# STM32.net
KiCad netlist of a schematic drawn in Altium Designer
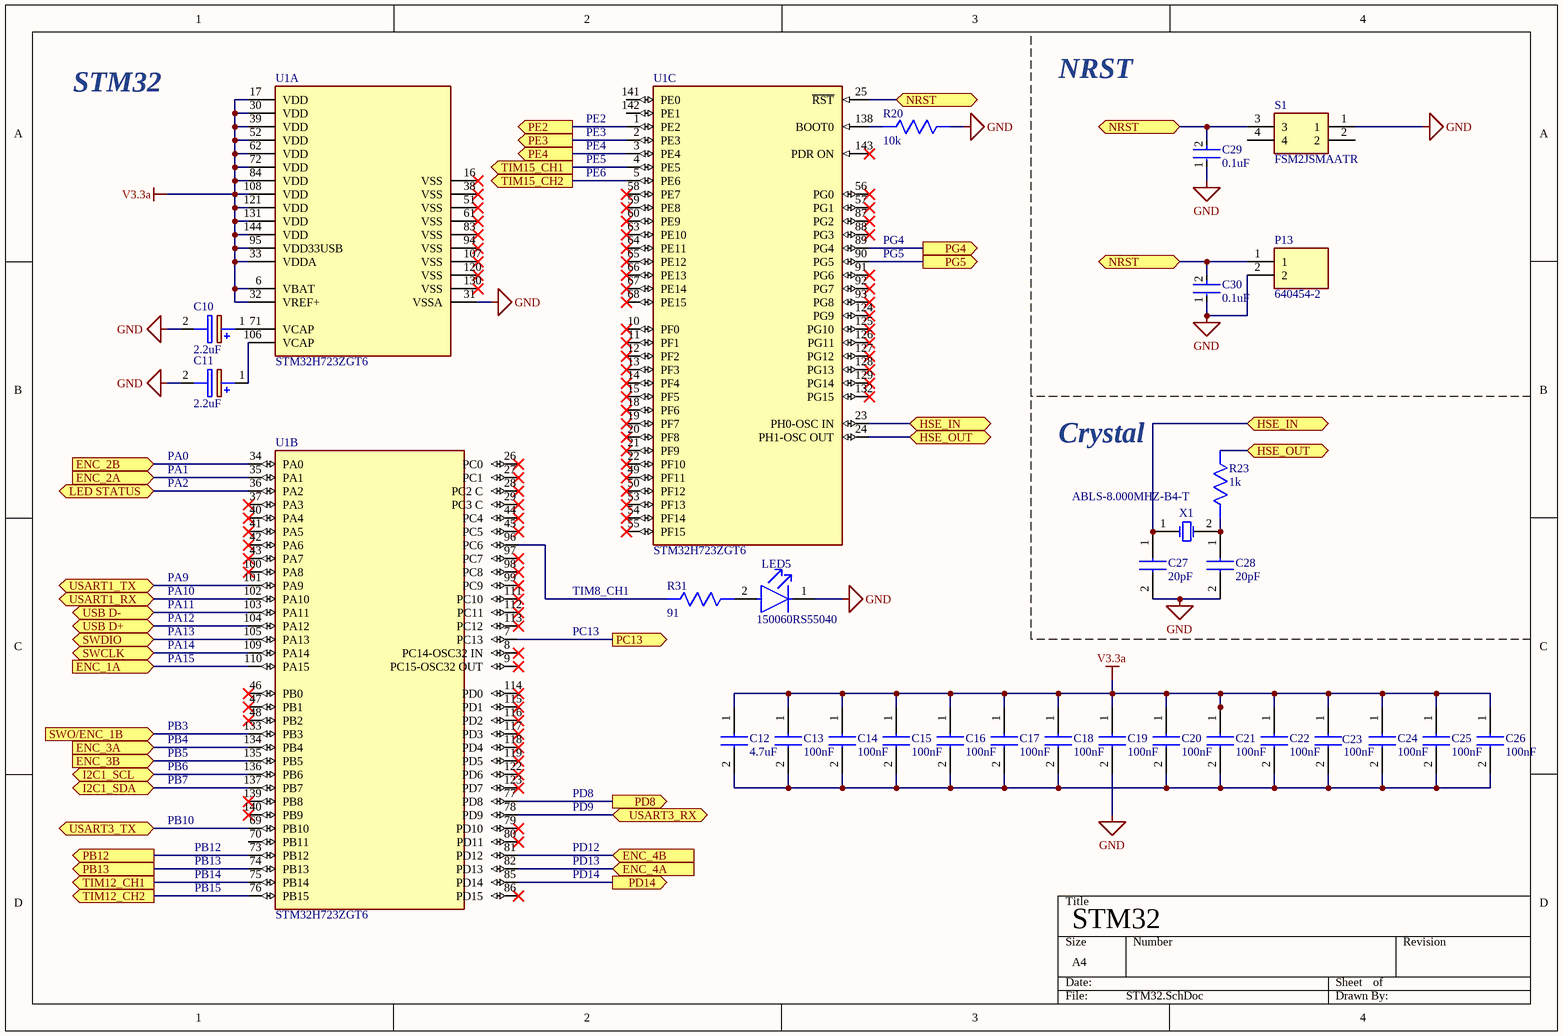
[diagram p0: STM32.SchDoc]

(export (version "E")
  (design (tool "Eeschema 10.0.6"))
  (components
    (comp (ref "C10")
      (value "2.2uF")
      (footprint "SamacSys:T491D")
      (description "Capacitor Polarised")
      (fields (field (name "MANUFACTURER_PART_NUMBER") "T491D225K050AH"))
      (libsource (lib "SamacSys") (part "T491D225K050AH"))
    )
    (comp (ref "C11")
      (value "2.2uF")
      (footprint "SamacSys:T491D")
      (description "Capacitor Polarised")
      (fields (field (name "MANUFACTURER_PART_NUMBER") "T491D225K050AH"))
      (libsource (lib "SamacSys") (part "T491D225K050AH"))
    )
    (comp (ref "C12")
      (value "4.7uF")
      (footprint "SamacSys:C1608_Commercial")
      (description "Capacitor")
      (fields (field (name "MANUFACTURER_PART_NUMBER") "C1608X5R1H104M080AA"))
      (libsource (lib "*") (part "C1608X5R1H104M080AA"))
    )
    (comp (ref "C13")
      (value "100nF")
      (footprint "SamacSys:C1608_Commercial")
      (description "Capacitor")
      (fields (field (name "MANUFACTURER_PART_NUMBER") "C1608X5R1H104M080AA"))
      (libsource (lib "*") (part "C1608X5R1H104M080AA"))
    )
    (comp (ref "C14")
      (value "100nF")
      (footprint "SamacSys:C1608_Commercial")
      (description "Capacitor")
      (fields (field (name "MANUFACTURER_PART_NUMBER") "C1608X5R1H104M080AA"))
      (libsource (lib "*") (part "C1608X5R1H104M080AA"))
    )
    (comp (ref "C15")
      (value "100nF")
      (footprint "SamacSys:C1608_Commercial")
      (description "Capacitor")
      (fields (field (name "MANUFACTURER_PART_NUMBER") "C1608X5R1H104M080AA"))
      (libsource (lib "*") (part "C1608X5R1H104M080AA"))
    )
    (comp (ref "C16")
      (value "100nF")
      (footprint "SamacSys:C1608_Commercial")
      (description "Capacitor")
      (fields (field (name "MANUFACTURER_PART_NUMBER") "C1608X5R1H104M080AA"))
      (libsource (lib "*") (part "C1608X5R1H104M080AA"))
    )
    (comp (ref "C17")
      (value "100nF")
      (footprint "SamacSys:C1608_Commercial")
      (description "Capacitor")
      (fields (field (name "MANUFACTURER_PART_NUMBER") "C1608X5R1H104M080AA"))
      (libsource (lib "*") (part "C1608X5R1H104M080AA"))
    )
    (comp (ref "C18")
      (value "100nF")
      (footprint "SamacSys:C1608_Commercial")
      (description "Capacitor")
      (fields (field (name "MANUFACTURER_PART_NUMBER") "C1608X5R1H104M080AA"))
      (libsource (lib "*") (part "C1608X5R1H104M080AA"))
    )
    (comp (ref "C19")
      (value "100nF")
      (footprint "SamacSys:C1608_Commercial")
      (description "Capacitor")
      (fields (field (name "MANUFACTURER_PART_NUMBER") "C1608X5R1H104M080AA"))
      (libsource (lib "*") (part "C1608X5R1H104M080AA"))
    )
    (comp (ref "C20")
      (value "100nF")
      (footprint "SamacSys:C1608_Commercial")
      (description "Capacitor")
      (fields (field (name "MANUFACTURER_PART_NUMBER") "C1608X5R1H104M080AA"))
      (libsource (lib "*") (part "C1608X5R1H104M080AA"))
    )
    (comp (ref "C21")
      (value "100nF")
      (footprint "SamacSys:C1608_Commercial")
      (description "Capacitor")
      (fields (field (name "MANUFACTURER_PART_NUMBER") "C1608X5R1H104M080AA"))
      (libsource (lib "*") (part "C1608X5R1H104M080AA"))
    )
    (comp (ref "C22")
      (value "100nF")
      (footprint "SamacSys:C1608_Commercial")
      (description "Capacitor")
      (fields (field (name "MANUFACTURER_PART_NUMBER") "C1608X5R1H104M080AA"))
      (libsource (lib "*") (part "C1608X5R1H104M080AA"))
    )
    (comp (ref "C23")
      (value "100nF")
      (footprint "SamacSys:C1608_Commercial")
      (description "Capacitor")
      (fields (field (name "MANUFACTURER_PART_NUMBER") "C1608X5R1H104M080AA"))
      (libsource (lib "*") (part "C1608X5R1H104M080AA"))
    )
    (comp (ref "C24")
      (value "100nF")
      (footprint "SamacSys:C1608_Commercial")
      (description "Capacitor")
      (fields (field (name "MANUFACTURER_PART_NUMBER") "C1608X5R1H104M080AA"))
      (libsource (lib "*") (part "C1608X5R1H104M080AA"))
    )
    (comp (ref "C25")
      (value "100nF")
      (footprint "SamacSys:C1608_Commercial")
      (description "Capacitor")
      (fields (field (name "MANUFACTURER_PART_NUMBER") "C1608X5R1H104M080AA"))
      (libsource (lib "*") (part "C1608X5R1H104M080AA"))
    )
    (comp (ref "C26")
      (value "100nF")
      (footprint "SamacSys:C1608_Commercial")
      (description "Capacitor")
      (fields (field (name "MANUFACTURER_PART_NUMBER") "C1608X5R1H104M080AA"))
      (libsource (lib "*") (part "C1608X5R1H104M080AA"))
    )
    (comp (ref "C27")
      (value "20pF")
      (footprint "SamacSys:CAPC1608X90N")
      (description "Capacitor")
      (fields
        (field (name "MANUFACTURER_PART_NUMBER") "06035A200FAT2A")
        (field (name "MOUSER PART NUMBER") "581-06035A200FAT2A")
      )
      (libsource (lib "*") (part "06035A200FAT2A"))
    )
    (comp (ref "C28")
      (value "20pF")
      (footprint "SamacSys:CAPC1608X90N")
      (description "Capacitor")
      (fields
        (field (name "MANUFACTURER_PART_NUMBER") "06035A200FAT2A")
        (field (name "MOUSER PART NUMBER") "581-06035A200FAT2A")
      )
      (libsource (lib "*") (part "06035A200FAT2A"))
    )
    (comp (ref "C29")
      (value "0.1uF")
      (footprint "FP-C1608-080-0_1-IPC_A")
      (description "Multilayer Ceramic Capacitors 100nF ±10% 50V X5R SMD 0603")
      (fields (field (name "TOLERANCE") "10%"))
      (libsource (lib "Altium Content Vault") (part "236180d848d6139a670b325ea6854c9"))
    )
    (comp (ref "C30")
      (value "0.1uF")
      (footprint "FP-C1608-080-0_1-IPC_A")
      (description "Multilayer Ceramic Capacitors 100nF ±10% 50V X5R SMD 0603")
      (fields (field (name "TOLERANCE") "10%"))
      (libsource (lib "Altium Content Vault") (part "236180d848d6139a670b325ea6854c9"))
    )
    (comp (ref "LED5")
      (value "150060RS55040")
      (footprint "FP-150060RS55040-MFG")
      (description "LED RED DIFFUSED 0603 SMD")
      (libsource (lib "Altium Content Vault") (part "8706943c75ba83719d021d2fdc84c58"))
    )
    (comp (ref "P13")
      (value "640454-2")
      (footprint "SamacSys:HDRV2W66P0X254_1X2_762X572X1003P")
      (description "Connector")
      (libsource (lib "*") (part "640454-2"))
    )
    (comp (ref "R20")
      (value "10k")
      (footprint "SamacSys:RESC1608X55N")
      (description "Resistor")
      (fields (field (name "MANUFACTURER_PART_NUMBER") "CMP0603-FX-1003ELF"))
      (libsource (lib "SamacSys") (part "CMP0603-FX-1003ELF"))
    )
    (comp (ref "R23")
      (value "1k")
      (footprint "SamacSys:RESC1608X55N")
      (description "Resistor")
      (fields (field (name "MANUFACTURER_PART_NUMBER") "CMP0603-FX-1003ELF"))
      (libsource (lib "SamacSys") (part "CMP0603-FX-1003ELF"))
    )
    (comp (ref "R31")
      (value "91")
      (footprint "SamacSys:RESC1608X55N")
      (description "Resistor")
      (fields (field (name "MANUFACTURER_PART_NUMBER") "CMP0603-FX-1003ELF"))
      (libsource (lib "SamacSys") (part "CMP0603-FX-1003ELF"))
    )
    (comp (ref "S1")
      (value "FSM2JSMAATR")
      (footprint "SamacSys:FSM2J_1")
      (description "Switch")
      (libsource (lib "SamacSys") (part "FSM2JSMAATR"))
    )
    (comp (ref "U1")
      (value "STM32H723ZGT6")
      (footprint "FP-LQFP144-1A-IPC_C")
      (description "IC MCU 32BIT 1MB FLASH 144LQFP")
      (libsource (lib "Altium Content Vault") (part "099c9e622ff36f7eb897f9cba6d1f51"))
    )
    (comp (ref "X1")
      (value "ABLS-8.000MHZ-B4-T")
      (footprint "ABRA-ABLS-14.7456MHZ-B2-T_V")
      (description "Low Profile Crystal, 8.0 MHz, +/- 30 ppm, -20 to 70 degC, 2-Pin SMD, RoHS, Tape and Reel")
      (fields (field (name "MANUFACTURER") "ABRACON") (field (name "TOLERANCE") "30PPM"))
      (libsource (lib "Altium Content Vault") (part "XTAL_1-2-2"))
    )
  )
  (nets
    (net (code "1") (name "/ENC_1A") (class "Default")
      (node (ref "U1") (pin "110") (pinfunction "PA15_110") (pintype "bidirectional"))
    )
    (net (code "2") (name "/ENC_2A") (class "Default")
      (node (ref "U1") (pin "35") (pinfunction "PA1_35") (pintype "bidirectional"))
    )
    (net (code "3") (name "/ENC_2B") (class "Default")
      (node (ref "U1") (pin "34") (pinfunction "PA0_34") (pintype "bidirectional"))
    )
    (net (code "4") (name "/ENC_3A") (class "Default")
      (node (ref "U1") (pin "134") (pinfunction "PB4_134") (pintype "bidirectional"))
    )
    (net (code "5") (name "/ENC_3B") (class "Default")
      (node (ref "U1") (pin "135") (pinfunction "PB5_135") (pintype "bidirectional"))
    )
    (net (code "6") (name "/ENC_4A") (class "Default")
      (node (ref "U1") (pin "82") (pinfunction "PD13_82") (pintype "bidirectional"))
    )
    (net (code "7") (name "/ENC_4B") (class "Default")
      (node (ref "U1") (pin "81") (pinfunction "PD12_81") (pintype "bidirectional"))
    )
    (net (code "8") (name "/HSE_IN") (class "Default")
      (node (ref "C27") (pin "1") (pinfunction "1_1") (pintype "passive"))
      (node (ref "U1") (pin "23") (pinfunction "PH0-OSC_IN_23") (pintype "bidirectional"))
      (node (ref "X1") (pin "1") (pinfunction "X1_1") (pintype "passive"))
    )
    (net (code "9") (name "/HSE_OUT") (class "Default")
      (node (ref "R23") (pin "2") (pinfunction "2_2") (pintype "passive"))
      (node (ref "U1") (pin "24") (pinfunction "PH1-OSC_OUT_24") (pintype "bidirectional"))
    )
    (net (code "10") (name "/I2C1_SCL") (class "Default")
      (node (ref "U1") (pin "136") (pinfunction "PB6_136") (pintype "bidirectional"))
    )
    (net (code "11") (name "/I2C1_SDA") (class "Default")
      (node (ref "U1") (pin "137") (pinfunction "PB7_137") (pintype "bidirectional"))
    )
    (net (code "12") (name "/LED STATUS") (class "Default")
      (node (ref "U1") (pin "36") (pinfunction "PA2_36") (pintype "bidirectional"))
    )
    (net (code "13") (name "/NRST") (class "Default")
      (node (ref "C29") (pin "2") (pinfunction "2_2") (pintype "passive"))
      (node (ref "C30") (pin "2") (pinfunction "2_2") (pintype "passive"))
      (node (ref "P13") (pin "1") (pinfunction "1_1") (pintype "passive"))
      (node (ref "S1") (pin "3") (pinfunction "3_3") (pintype "passive"))
      (node (ref "U1") (pin "25") (pinfunction "~{RST}_25") (pintype "input"))
    )
    (net (code "14") (name "/PB12") (class "Default")
      (node (ref "U1") (pin "73") (pinfunction "PB12_73") (pintype "bidirectional"))
    )
    (net (code "15") (name "/PB13") (class "Default")
      (node (ref "U1") (pin "74") (pinfunction "PB13_74") (pintype "bidirectional"))
    )
    (net (code "16") (name "/PC13") (class "Default")
      (node (ref "U1") (pin "7") (pinfunction "PC13_7") (pintype "bidirectional"))
    )
    (net (code "17") (name "/PD8") (class "Default")
      (node (ref "U1") (pin "77") (pinfunction "PD8_77") (pintype "bidirectional"))
    )
    (net (code "18") (name "/PD14") (class "Default")
      (node (ref "U1") (pin "85") (pinfunction "PD14_85") (pintype "bidirectional"))
    )
    (net (code "19") (name "/PE2") (class "Default")
      (node (ref "U1") (pin "1") (pinfunction "PE2_1") (pintype "bidirectional"))
    )
    (net (code "20") (name "/PE3") (class "Default")
      (node (ref "U1") (pin "2") (pinfunction "PE3_2") (pintype "bidirectional"))
    )
    (net (code "21") (name "/PE4") (class "Default")
      (node (ref "U1") (pin "3") (pinfunction "PE4_3") (pintype "bidirectional"))
    )
    (net (code "22") (name "/PG4") (class "Default")
      (node (ref "U1") (pin "89") (pinfunction "PG4_89") (pintype "bidirectional"))
    )
    (net (code "23") (name "/PG5") (class "Default")
      (node (ref "U1") (pin "90") (pinfunction "PG5_90") (pintype "bidirectional"))
    )
    (net (code "24") (name "/SWCLK") (class "Default")
      (node (ref "U1") (pin "109") (pinfunction "PA14_109") (pintype "bidirectional"))
    )
    (net (code "25") (name "/SWDIO") (class "Default")
      (node (ref "U1") (pin "105") (pinfunction "PA13_105") (pintype "bidirectional"))
    )
    (net (code "26") (name "/SWO{slash}ENC_1B") (class "Default")
      (node (ref "U1") (pin "133") (pinfunction "PB3_133") (pintype "bidirectional"))
    )
    (net (code "27") (name "/TIM12_CH1") (class "Default")
      (node (ref "U1") (pin "75") (pinfunction "PB14_75") (pintype "bidirectional"))
    )
    (net (code "28") (name "/TIM12_CH2") (class "Default")
      (node (ref "U1") (pin "76") (pinfunction "PB15_76") (pintype "bidirectional"))
    )
    (net (code "29") (name "/TIM15_CH1") (class "Default")
      (node (ref "U1") (pin "4") (pinfunction "PE5_4") (pintype "bidirectional"))
    )
    (net (code "30") (name "/TIM15_CH2") (class "Default")
      (node (ref "U1") (pin "5") (pinfunction "PE6_5") (pintype "bidirectional"))
    )
    (net (code "31") (name "/USART1_RX") (class "Default")
      (node (ref "U1") (pin "102") (pinfunction "PA10_102") (pintype "bidirectional"))
    )
    (net (code "32") (name "/USART1_TX") (class "Default")
      (node (ref "U1") (pin "101") (pinfunction "PA9_101") (pintype "bidirectional"))
    )
    (net (code "33") (name "/USART3_RX") (class "Default")
      (node (ref "U1") (pin "78") (pinfunction "PD9_78") (pintype "bidirectional"))
    )
    (net (code "34") (name "/USART3_TX") (class "Default")
      (node (ref "U1") (pin "69") (pinfunction "PB10_69") (pintype "bidirectional"))
    )
    (net (code "35") (name "/USB D+") (class "Default")
      (node (ref "U1") (pin "104") (pinfunction "PA12_104") (pintype "bidirectional"))
    )
    (net (code "36") (name "/USB D-") (class "Default")
      (node (ref "U1") (pin "103") (pinfunction "PA11_103") (pintype "bidirectional"))
    )
    (net (code "37") (name "GND") (class "Default")
      (node (ref "C10") (pin "2") (pinfunction "-_2") (pintype "passive"))
      (node (ref "C11") (pin "2") (pinfunction "-_2") (pintype "passive"))
      (node (ref "C19") (pin "2") (pinfunction "2_2") (pintype "passive"))
      (node (ref "C27") (pin "2") (pinfunction "2_2") (pintype "passive"))
      (node (ref "C28") (pin "2") (pinfunction "2_2") (pintype "passive"))
      (node (ref "C29") (pin "1") (pinfunction "1_1") (pintype "passive"))
      (node (ref "C30") (pin "1") (pinfunction "1_1") (pintype "passive"))
      (node (ref "LED5") (pin "1") (pinfunction "C_1") (pintype "passive"))
      (node (ref "P13") (pin "2") (pinfunction "2_2") (pintype "passive"))
      (node (ref "R20") (pin "2") (pinfunction "2_2") (pintype "passive"))
      (node (ref "S1") (pin "1") (pinfunction "1_1") (pintype "passive"))
      (node (ref "U1") (pin "31") (pinfunction "VSSA_31") (pintype "power_in"))
    )
    (net (code "38") (name "Net-(C10-+)") (class "Default")
      (node (ref "C10") (pin "1") (pinfunction "+_1") (pintype "passive"))
      (node (ref "U1") (pin "71") (pinfunction "VCAP_71") (pintype "power_in"))
    )
    (net (code "39") (name "Net-(C11-+)") (class "Default")
      (node (ref "C11") (pin "1") (pinfunction "+_1") (pintype "passive"))
      (node (ref "U1") (pin "106") (pinfunction "VCAP_106") (pintype "power_in"))
    )
    (net (code "40") (name "Net-(C12-Pad2)") (class "Default")
      (node (ref "C12") (pin "2") (pinfunction "2_2") (pintype "passive"))
      (node (ref "C13") (pin "2") (pinfunction "2_2") (pintype "passive"))
      (node (ref "C14") (pin "2") (pinfunction "2_2") (pintype "passive"))
      (node (ref "C15") (pin "2") (pinfunction "2_2") (pintype "passive"))
      (node (ref "C16") (pin "2") (pinfunction "2_2") (pintype "passive"))
      (node (ref "C17") (pin "2") (pinfunction "2_2") (pintype "passive"))
      (node (ref "C18") (pin "2") (pinfunction "2_2") (pintype "passive"))
      (node (ref "C20") (pin "2") (pinfunction "2_2") (pintype "passive"))
      (node (ref "C21") (pin "2") (pinfunction "2_2") (pintype "passive"))
      (node (ref "C22") (pin "2") (pinfunction "2_2") (pintype "passive"))
      (node (ref "C23") (pin "2") (pinfunction "2_2") (pintype "passive"))
      (node (ref "C24") (pin "2") (pinfunction "2_2") (pintype "passive"))
      (node (ref "C25") (pin "2") (pinfunction "2_2") (pintype "passive"))
      (node (ref "C26") (pin "2") (pinfunction "2_2") (pintype "passive"))
    )
    (net (code "41") (name "Net-(LED5-A)") (class "Default")
      (node (ref "LED5") (pin "2") (pinfunction "A_2") (pintype "passive"))
      (node (ref "R31") (pin "2") (pinfunction "2_2") (pintype "passive"))
    )
    (net (code "42") (name "Net-(U1B-PC6)") (class "Default")
      (node (ref "R31") (pin "1") (pinfunction "1_1") (pintype "passive"))
      (node (ref "U1") (pin "96") (pinfunction "PC6_96") (pintype "bidirectional"))
    )
    (net (code "43") (name "Net-(U1C-BOOT0)") (class "Default")
      (node (ref "R20") (pin "1") (pinfunction "1_1") (pintype "passive"))
      (node (ref "U1") (pin "138") (pinfunction "BOOT0_138") (pintype "input"))
    )
    (net (code "44") (name "Net-(X1-X2)") (class "Default")
      (node (ref "C28") (pin "1") (pinfunction "1_1") (pintype "passive"))
      (node (ref "R23") (pin "1") (pinfunction "1_1") (pintype "passive"))
      (node (ref "X1") (pin "2") (pinfunction "X2_2") (pintype "passive"))
    )
    (net (code "45") (name "V3.3a") (class "Default")
      (node (ref "C12") (pin "1") (pinfunction "1_1") (pintype "passive"))
      (node (ref "C13") (pin "1") (pinfunction "1_1") (pintype "passive"))
      (node (ref "C14") (pin "1") (pinfunction "1_1") (pintype "passive"))
      (node (ref "C15") (pin "1") (pinfunction "1_1") (pintype "passive"))
      (node (ref "C16") (pin "1") (pinfunction "1_1") (pintype "passive"))
      (node (ref "C17") (pin "1") (pinfunction "1_1") (pintype "passive"))
      (node (ref "C18") (pin "1") (pinfunction "1_1") (pintype "passive"))
      (node (ref "C19") (pin "1") (pinfunction "1_1") (pintype "passive"))
      (node (ref "C20") (pin "1") (pinfunction "1_1") (pintype "passive"))
      (node (ref "C21") (pin "1") (pinfunction "1_1") (pintype "passive"))
      (node (ref "C22") (pin "1") (pinfunction "1_1") (pintype "passive"))
      (node (ref "C23") (pin "1") (pinfunction "1_1") (pintype "passive"))
      (node (ref "C24") (pin "1") (pinfunction "1_1") (pintype "passive"))
      (node (ref "C25") (pin "1") (pinfunction "1_1") (pintype "passive"))
      (node (ref "C26") (pin "1") (pinfunction "1_1") (pintype "passive"))
      (node (ref "U1") (pin "108") (pinfunction "VDD_108") (pintype "power_in"))
      (node (ref "U1") (pin "121") (pinfunction "VDD_121") (pintype "power_in"))
      (node (ref "U1") (pin "131") (pinfunction "VDD_131") (pintype "power_in"))
      (node (ref "U1") (pin "144") (pinfunction "VDD_144") (pintype "power_in"))
      (node (ref "U1") (pin "17") (pinfunction "VDD_17") (pintype "power_in"))
      (node (ref "U1") (pin "30") (pinfunction "VDD_30") (pintype "power_in"))
      (node (ref "U1") (pin "32") (pinfunction "VREF+_32") (pintype "power_in"))
      (node (ref "U1") (pin "33") (pinfunction "VDDA_33") (pintype "power_in"))
      (node (ref "U1") (pin "39") (pinfunction "VDD_39") (pintype "power_in"))
      (node (ref "U1") (pin "52") (pinfunction "VDD_52") (pintype "power_in"))
      (node (ref "U1") (pin "6") (pinfunction "VBAT_6") (pintype "power_in"))
      (node (ref "U1") (pin "62") (pinfunction "VDD_62") (pintype "power_in"))
      (node (ref "U1") (pin "72") (pinfunction "VDD_72") (pintype "power_in"))
      (node (ref "U1") (pin "84") (pinfunction "VDD_84") (pintype "power_in"))
      (node (ref "U1") (pin "95") (pinfunction "VDD33USB_95") (pintype "power_in"))
    )
    (net (code "46") (name "unconnected-(S1-Pad2)") (class "Default")
      (node (ref "S1") (pin "2") (pinfunction "2_2") (pintype "passive"))
    )
    (net (code "47") (name "unconnected-(S1-Pad4)") (class "Default")
      (node (ref "S1") (pin "4") (pinfunction "4_4") (pintype "passive"))
    )
    (net (code "48") (name "unconnected-(U1A-VSS-Pad16)") (class "Default")
      (node (ref "U1") (pin "16") (pinfunction "VSS_16") (pintype "power_in+no_connect"))
    )
    (net (code "49") (name "unconnected-(U1A-VSS-Pad38)") (class "Default")
      (node (ref "U1") (pin "38") (pinfunction "VSS_38") (pintype "power_in+no_connect"))
    )
    (net (code "50") (name "unconnected-(U1A-VSS-Pad51)") (class "Default")
      (node (ref "U1") (pin "51") (pinfunction "VSS_51") (pintype "power_in+no_connect"))
    )
    (net (code "51") (name "unconnected-(U1A-VSS-Pad61)") (class "Default")
      (node (ref "U1") (pin "61") (pinfunction "VSS_61") (pintype "power_in+no_connect"))
    )
    (net (code "52") (name "unconnected-(U1A-VSS-Pad83)") (class "Default")
      (node (ref "U1") (pin "83") (pinfunction "VSS_83") (pintype "power_in+no_connect"))
    )
    (net (code "53") (name "unconnected-(U1A-VSS-Pad94)") (class "Default")
      (node (ref "U1") (pin "94") (pinfunction "VSS_94") (pintype "power_in+no_connect"))
    )
    (net (code "54") (name "unconnected-(U1A-VSS-Pad107)") (class "Default")
      (node (ref "U1") (pin "107") (pinfunction "VSS_107") (pintype "power_in+no_connect"))
    )
    (net (code "55") (name "unconnected-(U1A-VSS-Pad120)") (class "Default")
      (node (ref "U1") (pin "120") (pinfunction "VSS_120") (pintype "power_in+no_connect"))
    )
    (net (code "56") (name "unconnected-(U1A-VSS-Pad130)") (class "Default")
      (node (ref "U1") (pin "130") (pinfunction "VSS_130") (pintype "power_in+no_connect"))
    )
    (net (code "57") (name "unconnected-(U1B-PA3-Pad37)") (class "Default")
      (node (ref "U1") (pin "37") (pinfunction "PA3_37") (pintype "bidirectional+no_connect"))
    )
    (net (code "58") (name "unconnected-(U1B-PA4-Pad40)") (class "Default")
      (node (ref "U1") (pin "40") (pinfunction "PA4_40") (pintype "bidirectional+no_connect"))
    )
    (net (code "59") (name "unconnected-(U1B-PA5-Pad41)") (class "Default")
      (node (ref "U1") (pin "41") (pinfunction "PA5_41") (pintype "bidirectional+no_connect"))
    )
    (net (code "60") (name "unconnected-(U1B-PA6-Pad42)") (class "Default")
      (node (ref "U1") (pin "42") (pinfunction "PA6_42") (pintype "bidirectional+no_connect"))
    )
    (net (code "61") (name "unconnected-(U1B-PA7-Pad43)") (class "Default")
      (node (ref "U1") (pin "43") (pinfunction "PA7_43") (pintype "bidirectional+no_connect"))
    )
    (net (code "62") (name "unconnected-(U1B-PA8-Pad100)") (class "Default")
      (node (ref "U1") (pin "100") (pinfunction "PA8_100") (pintype "bidirectional+no_connect"))
    )
    (net (code "63") (name "unconnected-(U1B-PB0-Pad46)") (class "Default")
      (node (ref "U1") (pin "46") (pinfunction "PB0_46") (pintype "bidirectional+no_connect"))
    )
    (net (code "64") (name "unconnected-(U1B-PB1-Pad47)") (class "Default")
      (node (ref "U1") (pin "47") (pinfunction "PB1_47") (pintype "bidirectional+no_connect"))
    )
    (net (code "65") (name "unconnected-(U1B-PB2-Pad48)") (class "Default")
      (node (ref "U1") (pin "48") (pinfunction "PB2_48") (pintype "bidirectional+no_connect"))
    )
    (net (code "66") (name "unconnected-(U1B-PB8-Pad139)") (class "Default")
      (node (ref "U1") (pin "139") (pinfunction "PB8_139") (pintype "bidirectional+no_connect"))
    )
    (net (code "67") (name "unconnected-(U1B-PB9-Pad140)") (class "Default")
      (node (ref "U1") (pin "140") (pinfunction "PB9_140") (pintype "bidirectional+no_connect"))
    )
    (net (code "68") (name "unconnected-(U1B-PB11-Pad70)") (class "Default")
      (node (ref "U1") (pin "70") (pinfunction "PB11_70") (pintype "bidirectional"))
    )
    (net (code "69") (name "unconnected-(U1B-PC0-Pad26)") (class "Default")
      (node (ref "U1") (pin "26") (pinfunction "PC0_26") (pintype "bidirectional+no_connect"))
    )
    (net (code "70") (name "unconnected-(U1B-PC1-Pad27)") (class "Default")
      (node (ref "U1") (pin "27") (pinfunction "PC1_27") (pintype "bidirectional+no_connect"))
    )
    (net (code "71") (name "unconnected-(U1B-PC2_C-Pad28)") (class "Default")
      (node (ref "U1") (pin "28") (pinfunction "PC2_C_28") (pintype "bidirectional+no_connect"))
    )
    (net (code "72") (name "unconnected-(U1B-PC3_C-Pad29)") (class "Default")
      (node (ref "U1") (pin "29") (pinfunction "PC3_C_29") (pintype "bidirectional+no_connect"))
    )
    (net (code "73") (name "unconnected-(U1B-PC4-Pad44)") (class "Default")
      (node (ref "U1") (pin "44") (pinfunction "PC4_44") (pintype "bidirectional+no_connect"))
    )
    (net (code "74") (name "unconnected-(U1B-PC5-Pad45)") (class "Default")
      (node (ref "U1") (pin "45") (pinfunction "PC5_45") (pintype "bidirectional+no_connect"))
    )
    (net (code "75") (name "unconnected-(U1B-PC7-Pad97)") (class "Default")
      (node (ref "U1") (pin "97") (pinfunction "PC7_97") (pintype "bidirectional+no_connect"))
    )
    (net (code "76") (name "unconnected-(U1B-PC8-Pad98)") (class "Default")
      (node (ref "U1") (pin "98") (pinfunction "PC8_98") (pintype "bidirectional+no_connect"))
    )
    (net (code "77") (name "unconnected-(U1B-PC9-Pad99)") (class "Default")
      (node (ref "U1") (pin "99") (pinfunction "PC9_99") (pintype "bidirectional+no_connect"))
    )
    (net (code "78") (name "unconnected-(U1B-PC10-Pad111)") (class "Default")
      (node (ref "U1") (pin "111") (pinfunction "PC10_111") (pintype "bidirectional+no_connect"))
    )
    (net (code "79") (name "unconnected-(U1B-PC11-Pad112)") (class "Default")
      (node (ref "U1") (pin "112") (pinfunction "PC11_112") (pintype "bidirectional+no_connect"))
    )
    (net (code "80") (name "unconnected-(U1B-PC12-Pad113)") (class "Default")
      (node (ref "U1") (pin "113") (pinfunction "PC12_113") (pintype "bidirectional+no_connect"))
    )
    (net (code "81") (name "unconnected-(U1B-PC14-OSC32_IN-Pad8)") (class "Default")
      (node (ref "U1") (pin "8") (pinfunction "PC14-OSC32_IN_8") (pintype "bidirectional+no_connect"))
    )
    (net (code "82") (name "unconnected-(U1B-PC15-OSC32_OUT-Pad9)") (class "Default")
      (node (ref "U1") (pin "9") (pinfunction "PC15-OSC32_OUT_9") (pintype "bidirectional+no_connect"))
    )
    (net (code "83") (name "unconnected-(U1B-PD0-Pad114)") (class "Default")
      (node (ref "U1") (pin "114") (pinfunction "PD0_114") (pintype "bidirectional+no_connect"))
    )
    (net (code "84") (name "unconnected-(U1B-PD1-Pad115)") (class "Default")
      (node (ref "U1") (pin "115") (pinfunction "PD1_115") (pintype "bidirectional+no_connect"))
    )
    (net (code "85") (name "unconnected-(U1B-PD2-Pad116)") (class "Default")
      (node (ref "U1") (pin "116") (pinfunction "PD2_116") (pintype "bidirectional+no_connect"))
    )
    (net (code "86") (name "unconnected-(U1B-PD3-Pad117)") (class "Default")
      (node (ref "U1") (pin "117") (pinfunction "PD3_117") (pintype "bidirectional+no_connect"))
    )
    (net (code "87") (name "unconnected-(U1B-PD4-Pad118)") (class "Default")
      (node (ref "U1") (pin "118") (pinfunction "PD4_118") (pintype "bidirectional+no_connect"))
    )
    (net (code "88") (name "unconnected-(U1B-PD5-Pad119)") (class "Default")
      (node (ref "U1") (pin "119") (pinfunction "PD5_119") (pintype "bidirectional+no_connect"))
    )
    (net (code "89") (name "unconnected-(U1B-PD6-Pad122)") (class "Default")
      (node (ref "U1") (pin "122") (pinfunction "PD6_122") (pintype "bidirectional+no_connect"))
    )
    (net (code "90") (name "unconnected-(U1B-PD7-Pad123)") (class "Default")
      (node (ref "U1") (pin "123") (pinfunction "PD7_123") (pintype "bidirectional+no_connect"))
    )
    (net (code "91") (name "unconnected-(U1B-PD10-Pad79)") (class "Default")
      (node (ref "U1") (pin "79") (pinfunction "PD10_79") (pintype "bidirectional+no_connect"))
    )
    (net (code "92") (name "unconnected-(U1B-PD11-Pad80)") (class "Default")
      (node (ref "U1") (pin "80") (pinfunction "PD11_80") (pintype "bidirectional+no_connect"))
    )
    (net (code "93") (name "unconnected-(U1B-PD15-Pad86)") (class "Default")
      (node (ref "U1") (pin "86") (pinfunction "PD15_86") (pintype "bidirectional+no_connect"))
    )
    (net (code "94") (name "unconnected-(U1C-PDR_ON-Pad143)") (class "Default")
      (node (ref "U1") (pin "143") (pinfunction "PDR_ON_143") (pintype "input+no_connect"))
    )
    (net (code "95") (name "unconnected-(U1C-PE0-Pad141)") (class "Default")
      (node (ref "U1") (pin "141") (pinfunction "PE0_141") (pintype "bidirectional"))
    )
    (net (code "96") (name "unconnected-(U1C-PE1-Pad142)") (class "Default")
      (node (ref "U1") (pin "142") (pinfunction "PE1_142") (pintype "bidirectional"))
    )
    (net (code "97") (name "unconnected-(U1C-PE7-Pad58)") (class "Default")
      (node (ref "U1") (pin "58") (pinfunction "PE7_58") (pintype "bidirectional+no_connect"))
    )
    (net (code "98") (name "unconnected-(U1C-PE8-Pad59)") (class "Default")
      (node (ref "U1") (pin "59") (pinfunction "PE8_59") (pintype "bidirectional+no_connect"))
    )
    (net (code "99") (name "unconnected-(U1C-PE9-Pad60)") (class "Default")
      (node (ref "U1") (pin "60") (pinfunction "PE9_60") (pintype "bidirectional+no_connect"))
    )
    (net (code "100") (name "unconnected-(U1C-PE10-Pad63)") (class "Default")
      (node (ref "U1") (pin "63") (pinfunction "PE10_63") (pintype "bidirectional+no_connect"))
    )
    (net (code "101") (name "unconnected-(U1C-PE11-Pad64)") (class "Default")
      (node (ref "U1") (pin "64") (pinfunction "PE11_64") (pintype "bidirectional+no_connect"))
    )
    (net (code "102") (name "unconnected-(U1C-PE12-Pad65)") (class "Default")
      (node (ref "U1") (pin "65") (pinfunction "PE12_65") (pintype "bidirectional+no_connect"))
    )
    (net (code "103") (name "unconnected-(U1C-PE13-Pad66)") (class "Default")
      (node (ref "U1") (pin "66") (pinfunction "PE13_66") (pintype "bidirectional+no_connect"))
    )
    (net (code "104") (name "unconnected-(U1C-PE14-Pad67)") (class "Default")
      (node (ref "U1") (pin "67") (pinfunction "PE14_67") (pintype "bidirectional+no_connect"))
    )
    (net (code "105") (name "unconnected-(U1C-PE15-Pad68)") (class "Default")
      (node (ref "U1") (pin "68") (pinfunction "PE15_68") (pintype "bidirectional+no_connect"))
    )
    (net (code "106") (name "unconnected-(U1C-PF0-Pad10)") (class "Default")
      (node (ref "U1") (pin "10") (pinfunction "PF0_10") (pintype "bidirectional+no_connect"))
    )
    (net (code "107") (name "unconnected-(U1C-PF1-Pad11)") (class "Default")
      (node (ref "U1") (pin "11") (pinfunction "PF1_11") (pintype "bidirectional+no_connect"))
    )
    (net (code "108") (name "unconnected-(U1C-PF2-Pad12)") (class "Default")
      (node (ref "U1") (pin "12") (pinfunction "PF2_12") (pintype "bidirectional+no_connect"))
    )
    (net (code "109") (name "unconnected-(U1C-PF3-Pad13)") (class "Default")
      (node (ref "U1") (pin "13") (pinfunction "PF3_13") (pintype "bidirectional+no_connect"))
    )
    (net (code "110") (name "unconnected-(U1C-PF4-Pad14)") (class "Default")
      (node (ref "U1") (pin "14") (pinfunction "PF4_14") (pintype "bidirectional+no_connect"))
    )
    (net (code "111") (name "unconnected-(U1C-PF5-Pad15)") (class "Default")
      (node (ref "U1") (pin "15") (pinfunction "PF5_15") (pintype "bidirectional+no_connect"))
    )
    (net (code "112") (name "unconnected-(U1C-PF6-Pad18)") (class "Default")
      (node (ref "U1") (pin "18") (pinfunction "PF6_18") (pintype "bidirectional+no_connect"))
    )
    (net (code "113") (name "unconnected-(U1C-PF7-Pad19)") (class "Default")
      (node (ref "U1") (pin "19") (pinfunction "PF7_19") (pintype "bidirectional+no_connect"))
    )
    (net (code "114") (name "unconnected-(U1C-PF8-Pad20)") (class "Default")
      (node (ref "U1") (pin "20") (pinfunction "PF8_20") (pintype "bidirectional+no_connect"))
    )
    (net (code "115") (name "unconnected-(U1C-PF9-Pad21)") (class "Default")
      (node (ref "U1") (pin "21") (pinfunction "PF9_21") (pintype "bidirectional+no_connect"))
    )
    (net (code "116") (name "unconnected-(U1C-PF10-Pad22)") (class "Default")
      (node (ref "U1") (pin "22") (pinfunction "PF10_22") (pintype "bidirectional+no_connect"))
    )
    (net (code "117") (name "unconnected-(U1C-PF11-Pad49)") (class "Default")
      (node (ref "U1") (pin "49") (pinfunction "PF11_49") (pintype "bidirectional+no_connect"))
    )
    (net (code "118") (name "unconnected-(U1C-PF12-Pad50)") (class "Default")
      (node (ref "U1") (pin "50") (pinfunction "PF12_50") (pintype "bidirectional+no_connect"))
    )
    (net (code "119") (name "unconnected-(U1C-PF13-Pad53)") (class "Default")
      (node (ref "U1") (pin "53") (pinfunction "PF13_53") (pintype "bidirectional+no_connect"))
    )
    (net (code "120") (name "unconnected-(U1C-PF14-Pad54)") (class "Default")
      (node (ref "U1") (pin "54") (pinfunction "PF14_54") (pintype "bidirectional+no_connect"))
    )
    (net (code "121") (name "unconnected-(U1C-PF15-Pad55)") (class "Default")
      (node (ref "U1") (pin "55") (pinfunction "PF15_55") (pintype "bidirectional+no_connect"))
    )
    (net (code "122") (name "unconnected-(U1C-PG0-Pad56)") (class "Default")
      (node (ref "U1") (pin "56") (pinfunction "PG0_56") (pintype "bidirectional+no_connect"))
    )
    (net (code "123") (name "unconnected-(U1C-PG1-Pad57)") (class "Default")
      (node (ref "U1") (pin "57") (pinfunction "PG1_57") (pintype "bidirectional+no_connect"))
    )
    (net (code "124") (name "unconnected-(U1C-PG2-Pad87)") (class "Default")
      (node (ref "U1") (pin "87") (pinfunction "PG2_87") (pintype "bidirectional+no_connect"))
    )
    (net (code "125") (name "unconnected-(U1C-PG3-Pad88)") (class "Default")
      (node (ref "U1") (pin "88") (pinfunction "PG3_88") (pintype "bidirectional+no_connect"))
    )
    (net (code "126") (name "unconnected-(U1C-PG6-Pad91)") (class "Default")
      (node (ref "U1") (pin "91") (pinfunction "PG6_91") (pintype "bidirectional+no_connect"))
    )
    (net (code "127") (name "unconnected-(U1C-PG7-Pad92)") (class "Default")
      (node (ref "U1") (pin "92") (pinfunction "PG7_92") (pintype "bidirectional+no_connect"))
    )
    (net (code "128") (name "unconnected-(U1C-PG8-Pad93)") (class "Default")
      (node (ref "U1") (pin "93") (pinfunction "PG8_93") (pintype "bidirectional+no_connect"))
    )
    (net (code "129") (name "unconnected-(U1C-PG9-Pad124)") (class "Default")
      (node (ref "U1") (pin "124") (pinfunction "PG9_124") (pintype "bidirectional+no_connect"))
    )
    (net (code "130") (name "unconnected-(U1C-PG10-Pad125)") (class "Default")
      (node (ref "U1") (pin "125") (pinfunction "PG10_125") (pintype "bidirectional+no_connect"))
    )
    (net (code "131") (name "unconnected-(U1C-PG11-Pad126)") (class "Default")
      (node (ref "U1") (pin "126") (pinfunction "PG11_126") (pintype "bidirectional+no_connect"))
    )
    (net (code "132") (name "unconnected-(U1C-PG12-Pad127)") (class "Default")
      (node (ref "U1") (pin "127") (pinfunction "PG12_127") (pintype "bidirectional+no_connect"))
    )
    (net (code "133") (name "unconnected-(U1C-PG13-Pad128)") (class "Default")
      (node (ref "U1") (pin "128") (pinfunction "PG13_128") (pintype "bidirectional+no_connect"))
    )
    (net (code "134") (name "unconnected-(U1C-PG14-Pad129)") (class "Default")
      (node (ref "U1") (pin "129") (pinfunction "PG14_129") (pintype "bidirectional+no_connect"))
    )
    (net (code "135") (name "unconnected-(U1C-PG15-Pad132)") (class "Default")
      (node (ref "U1") (pin "132") (pinfunction "PG15_132") (pintype "bidirectional+no_connect"))
    )
  )
)
